# 09B-11.net
KiCad netlist of a schematic drawn in EAGLE
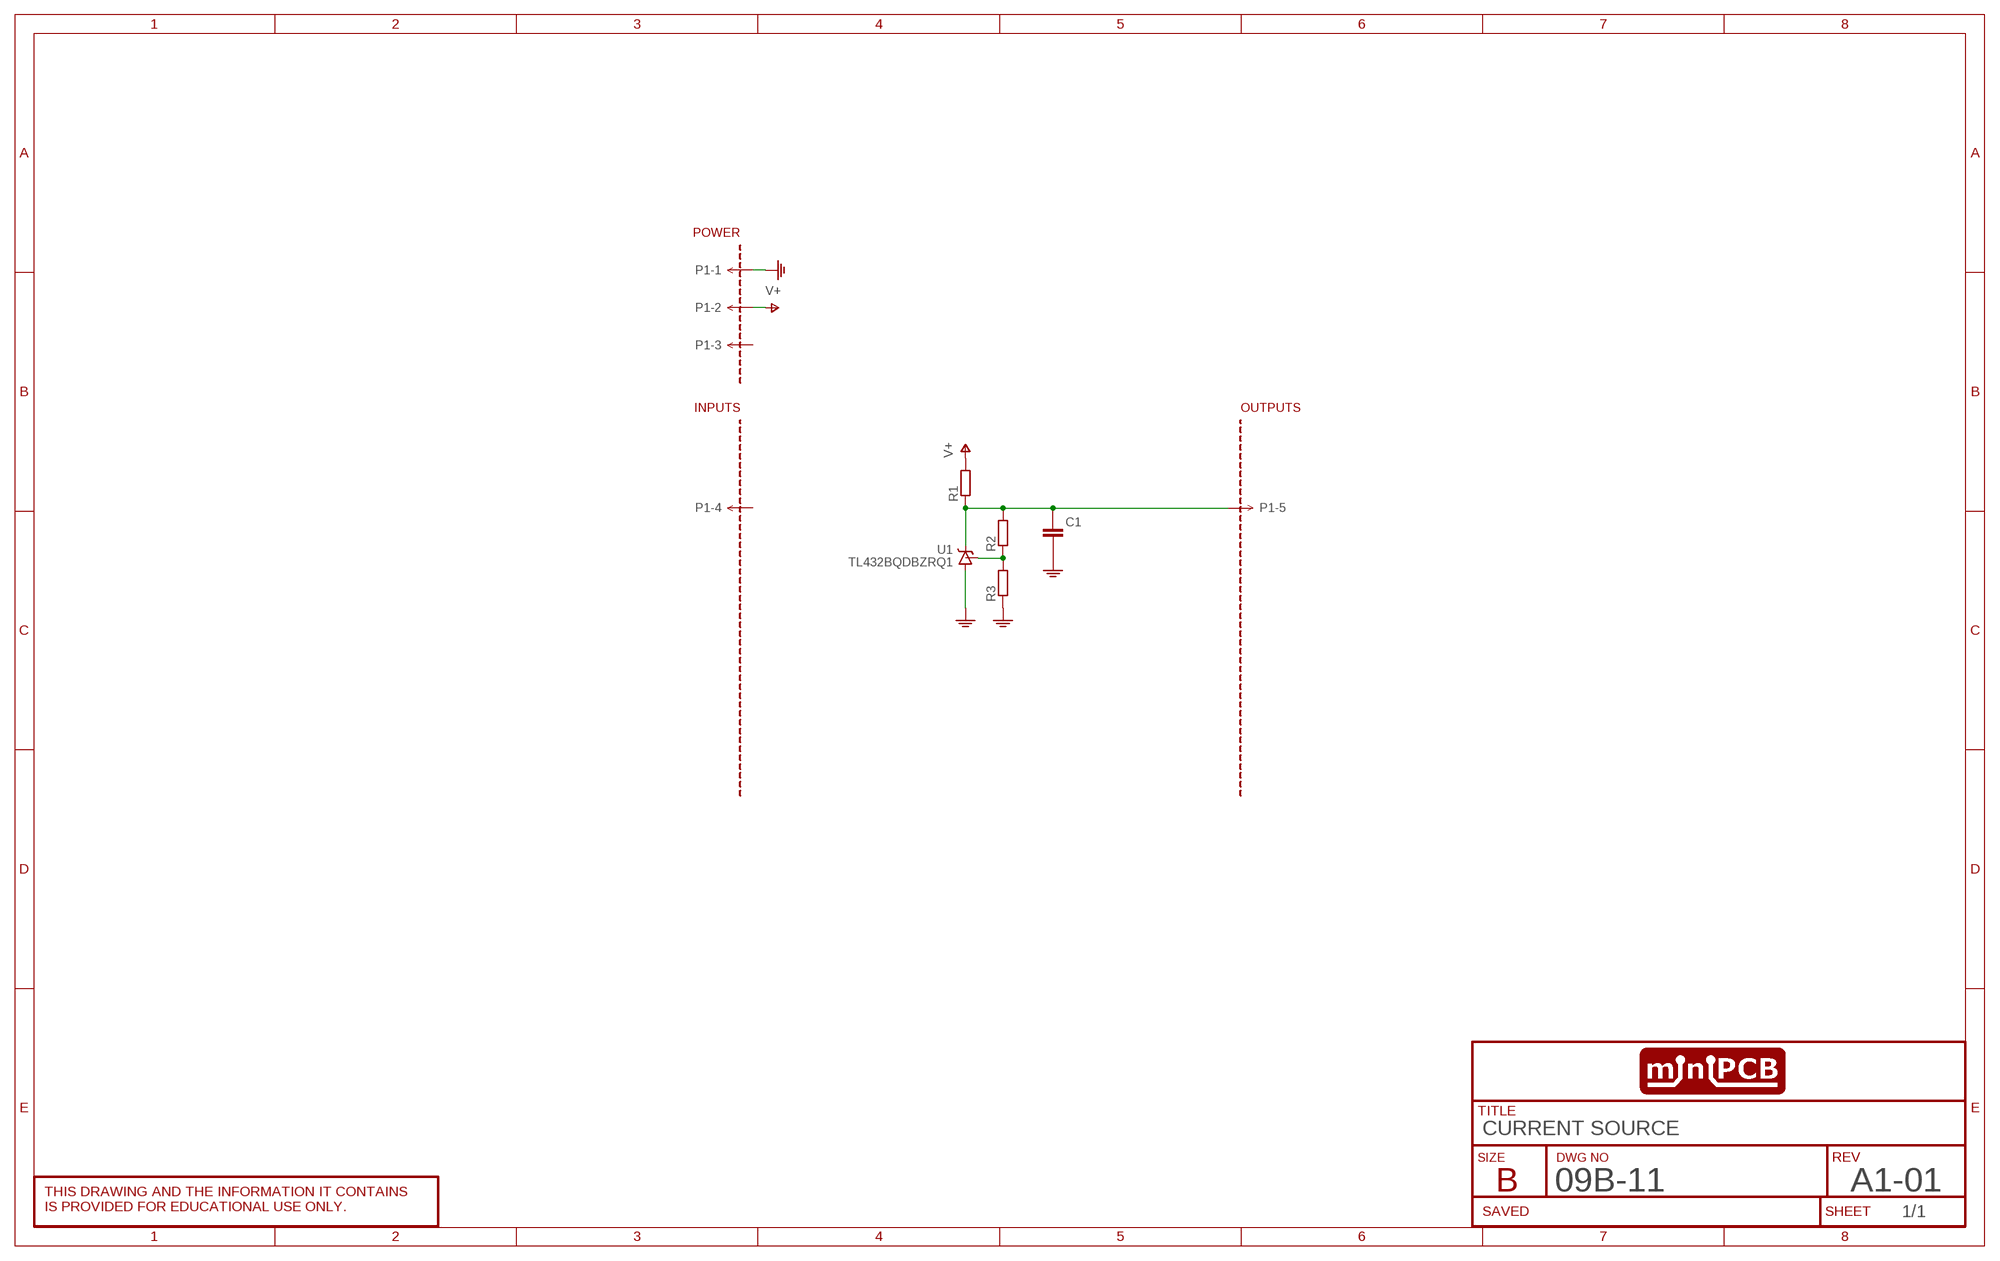
[diagram p0: schematic, sheet 1]

(export (version "E")
  (design (tool "Eeschema 10.0.6"))
  (components
    (comp (ref "C1")
      (value "CAPACITORSMD")
      (footprint "eagle-import:C0805")
      (libsource (lib "eagle-import") (part "CAPACITORSMD"))
    )
    (comp (ref "P1")
      (value "MINIPCB_5P5P")
      (footprint "eagle-import:PINS_1X5")
      (libsource (lib "eagle-import") (part "MINIPCB_5P5P"))
    )
    (comp (ref "PCB1")
      (value "MINIPCB_0PPCB20-20")
      (footprint "eagle-import:PCB20-20")
      (fields
        (field (name "PART_NUMBER") "09B-11")
        (field (name "REVISION") "A1-01")
        (field (name "TITLE") "TL432-EVAL")
      )
      (libsource (lib "eagle-import") (part "MINIPCB_0PPCB20-20"))
    )
    (comp (ref "R1")
      (value "RESISTORSMD")
      (footprint "eagle-import:R0805")
      (libsource (lib "eagle-import") (part "RESISTORSMD"))
    )
    (comp (ref "R2")
      (value "RESISTORSMD")
      (footprint "eagle-import:R0805")
      (libsource (lib "eagle-import") (part "RESISTORSMD"))
    )
    (comp (ref "R3")
      (value "RESISTORSMD")
      (footprint "eagle-import:R0805")
      (libsource (lib "eagle-import") (part "RESISTORSMD"))
    )
    (comp (ref "U1")
      (value "TL432BQDBZRQ1")
      (footprint "eagle-import:SOT95P237X112-3N")
      (fields (field (name "MF") "Texas Instruments"))
      (libsource (lib "eagle-import") (part "TL432BQDBZRQ1"))
    )
  )
  (nets
    (net (code "1") (name "GND") (class "Default")
      (node (ref "C1") (pin "2ASDF") (pinfunction "-_2ASDF") (pintype "passive"))
      (node (ref "P1") (pin "1") (pinfunction "1_1") (pintype "bidirectional"))
      (node (ref "R3") (pin "1") (pinfunction "1_1") (pintype "passive"))
      (node (ref "U1") (pin "3") (pinfunction "A_3") (pintype "passive"))
    )
    (net (code "2") (name "Net-(C1-+)") (class "Default")
      (node (ref "C1") (pin "1ASD") (pinfunction "+_1ASD") (pintype "passive"))
      (node (ref "P1") (pin "5") (pinfunction "1_5") (pintype "bidirectional"))
      (node (ref "R1") (pin "1") (pinfunction "1_1") (pintype "passive"))
      (node (ref "R2") (pin "2") (pinfunction "2_2") (pintype "passive"))
      (node (ref "U1") (pin "1") (pinfunction "C_1") (pintype "passive"))
    )
    (net (code "3") (name "Net-(U1-REF)") (class "Default")
      (node (ref "R2") (pin "1") (pinfunction "1_1") (pintype "passive"))
      (node (ref "R3") (pin "2") (pinfunction "2_2") (pintype "passive"))
      (node (ref "U1") (pin "2") (pinfunction "REF_2") (pintype "bidirectional"))
    )
    (net (code "4") (name "V+") (class "Default")
      (node (ref "P1") (pin "2") (pinfunction "1_2") (pintype "bidirectional"))
      (node (ref "R1") (pin "2") (pinfunction "2_2") (pintype "passive"))
    )
    (net (code "5") (name "unconnected-(P1C-1-Pad3)") (class "Default")
      (node (ref "P1") (pin "3") (pinfunction "1_3") (pintype "bidirectional"))
    )
    (net (code "6") (name "unconnected-(P1D-1-Pad4)") (class "Default")
      (node (ref "P1") (pin "4") (pinfunction "1_4") (pintype "bidirectional"))
    )
  )
)
